# McPiFace-Audio-V1_1.net
KiCad netlist of a schematic drawn in EAGLE
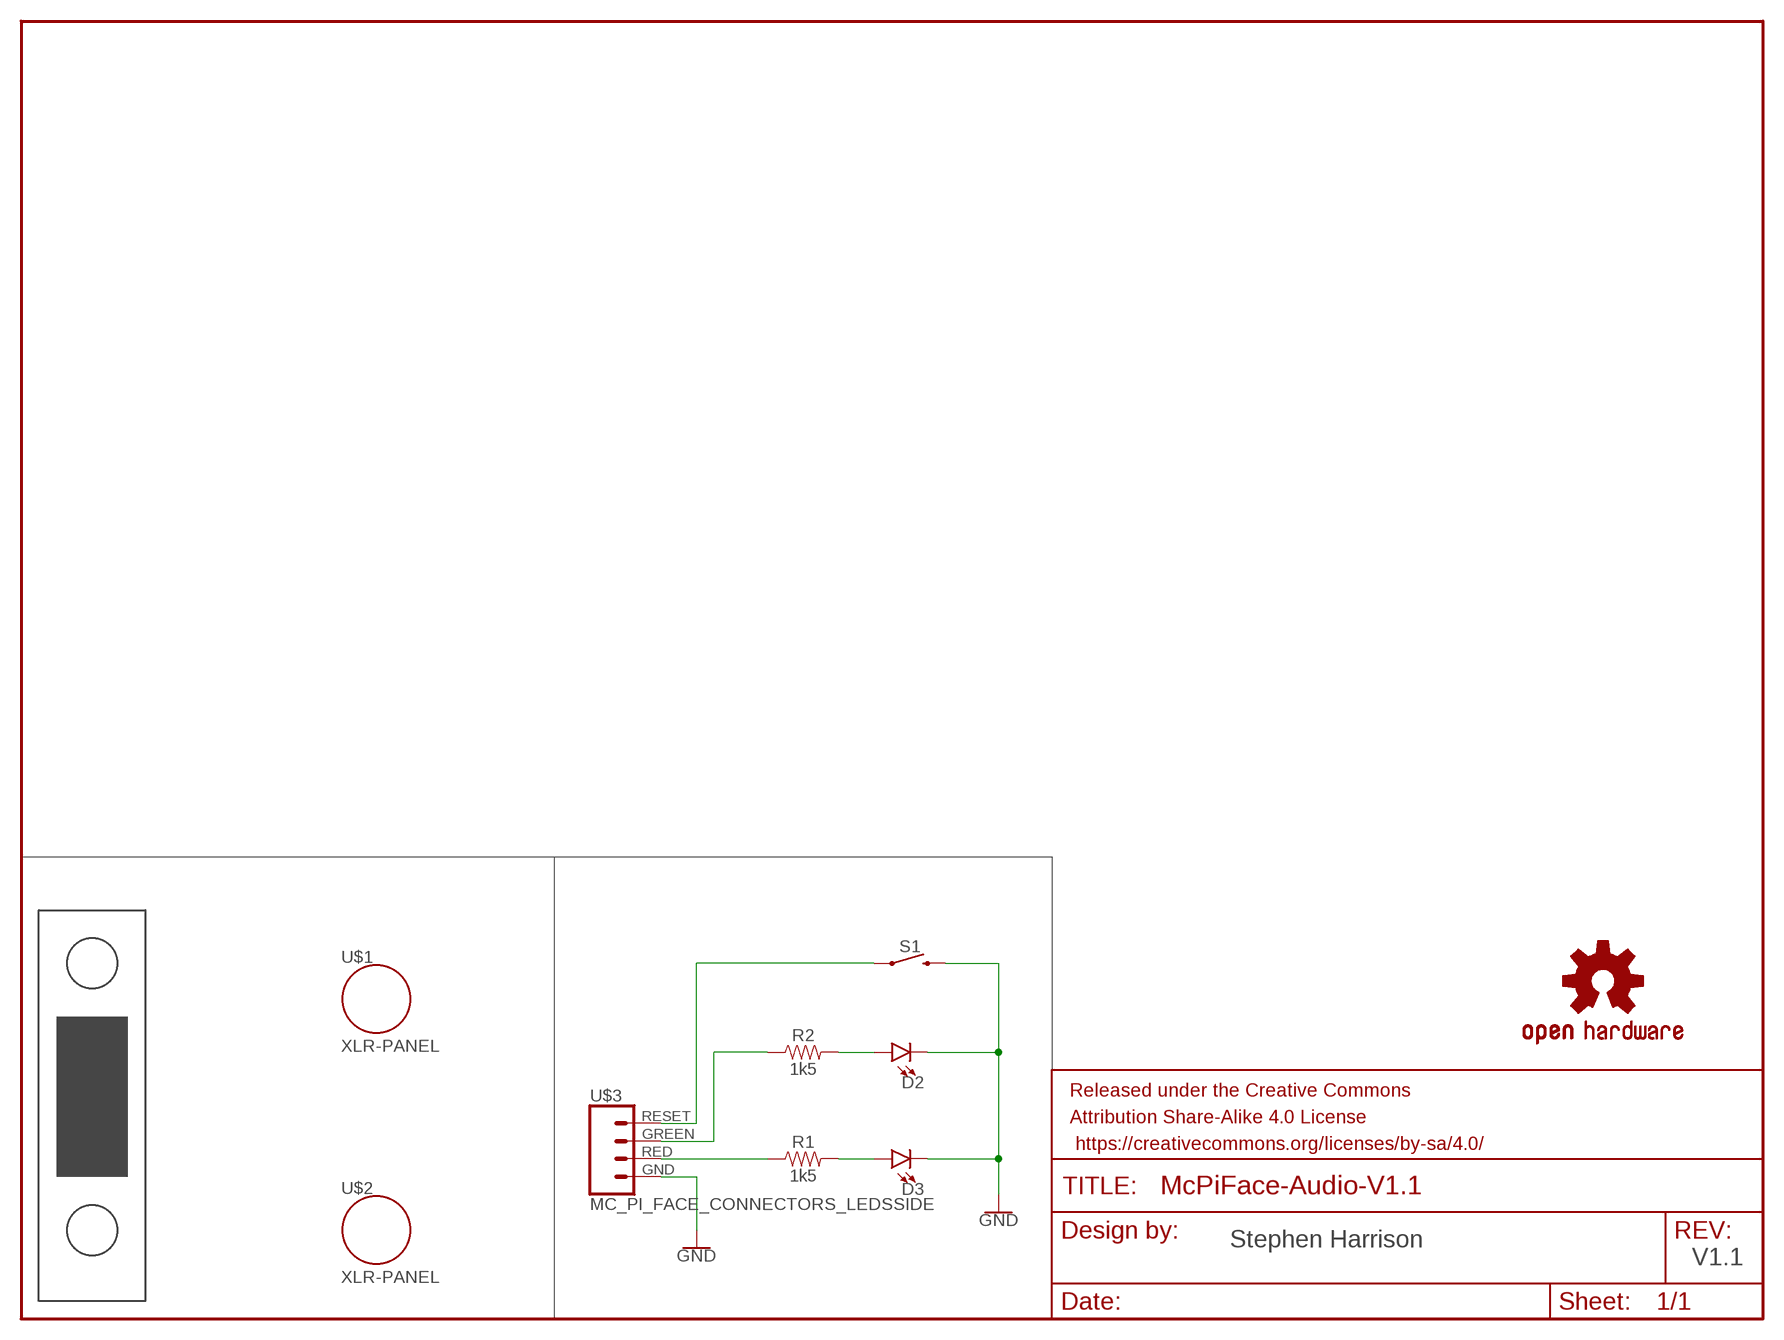
[diagram p0: schematic, sheet 1]

(export (version "E")
  (design (tool "Eeschema 10.0.6"))
  (components
    (comp (ref "D2")
      (value "LEDLED-1206-BOTTOM-2.0MM-GREEN")
      (footprint "eagle-import:LED-1206-BOTTOM-2.0MM")
      (libsource (lib "eagle-import") (part "LEDLED-1206-BOTTOM-2.0MM-GREEN"))
    )
    (comp (ref "D3")
      (value "LEDLED-1206-BOTTOM-2.0MM-RED")
      (footprint "eagle-import:LED-1206-BOTTOM-2.0MM")
      (libsource (lib "eagle-import") (part "LEDLED-1206-BOTTOM-2.0MM-RED"))
    )
    (comp (ref "FRAME1")
      (value "FRAME-LETTER")
      (footprint "eagle-import:CREATIVE_COMMONS")
      (libsource (lib "eagle-import") (part "FRAME-LETTER"))
    )
    (comp (ref "LOGO1")
      (value "OSHW-LOGOL")
      (footprint "eagle-import:OSHW-LOGO-L")
      (libsource (lib "eagle-import") (part "OSHW-LOGOL"))
    )
    (comp (ref "R1")
      (value "1k5")
      (footprint "eagle-import:0805")
      (libsource (lib "eagle-import") (part "RESISTOR0805"))
    )
    (comp (ref "R2")
      (value "1k5")
      (footprint "eagle-import:0805")
      (libsource (lib "eagle-import") (part "RESISTOR0805"))
    )
    (comp (ref "S1")
      (value "MOMENTARY-SWITCH-SPSTTACKTILE_SWITCH_PTH_6.0MM_NO_TOP_RESIST")
      (footprint "eagle-import:TACTILE_SWITCH_PTH_6.0MM_NO_TOP_RESIST")
      (libsource (lib "eagle-import") (part "MOMENTARY-SWITCH-SPSTTACKTILE_SWITCH_PTH_6.0MM_NO_TOP_RESIST"))
    )
    (comp (ref "U$1")
      (value "XLR-PANEL")
      (footprint "eagle-import:NC3FD-V-BAG-PANEL-COUTOUT")
      (libsource (lib "eagle-import") (part "XLR-PANEL"))
    )
    (comp (ref "U$2")
      (value "XLR-PANEL")
      (footprint "eagle-import:NC3FD-V-BAG-PANEL-COUTOUT")
      (libsource (lib "eagle-import") (part "XLR-PANEL"))
    )
    (comp (ref "U$3")
      (value "MC_PI_FACE_CONNECTORS_LEDSSIDE")
      (footprint "eagle-import:JST-4-SH-1.0MM-SIDE")
      (fields (field (name "MFG") "SM04B-SRSS-TB(LF)(SN)"))
      (libsource (lib "eagle-import") (part "MC_PI_FACE_CONNECTORS_LEDSSIDE"))
    )
    (comp (ref "U$4")
      (value "MC_PI_FACE_PANELDOUBLE")
      (footprint "eagle-import:MC_PI_DOUBLE_FACE")
      (libsource (lib "eagle-import") (part "MC_PI_FACE_PANELDOUBLE"))
    )
  )
  (nets
    (net (code "1") (name "GND") (class "Default")
      (node (ref "D2") (pin "C") (pinfunction "C_C") (pintype "passive"))
      (node (ref "D3") (pin "C") (pinfunction "C_C") (pintype "passive"))
      (node (ref "S1") (pin "3") (pinfunction "2_3") (pintype "passive"))
      (node (ref "U$3") (pin "GND") (pinfunction "GND_GND") (pintype "power_in"))
    )
    (net (code "2") (name "Net-(D2-PadA)") (class "Default")
      (node (ref "D2") (pin "A") (pinfunction "A_A") (pintype "passive"))
      (node (ref "R2") (pin "2") (pinfunction "2_2") (pintype "passive"))
    )
    (net (code "3") (name "Net-(D3-PadA)") (class "Default")
      (node (ref "D3") (pin "A") (pinfunction "A_A") (pintype "passive"))
      (node (ref "R1") (pin "2") (pinfunction "2_2") (pintype "passive"))
    )
    (net (code "4") (name "Net-(R1-Pad1)") (class "Default")
      (node (ref "R1") (pin "1") (pinfunction "1_1") (pintype "passive"))
      (node (ref "U$3") (pin "RED") (pinfunction "RED_RED") (pintype "passive"))
    )
    (net (code "5") (name "Net-(R2-Pad1)") (class "Default")
      (node (ref "R2") (pin "1") (pinfunction "1_1") (pintype "passive"))
      (node (ref "U$3") (pin "GREEN") (pinfunction "GREEN_GREEN") (pintype "passive"))
    )
    (net (code "6") (name "Net-(S1-Pad1)") (class "Default")
      (node (ref "S1") (pin "1") (pinfunction "1_1") (pintype "passive"))
      (node (ref "U$3") (pin "RESET") (pinfunction "RESET_RESET") (pintype "passive"))
    )
  )
)
